# POWER.net
KiCad netlist of a schematic drawn in Altium Designer
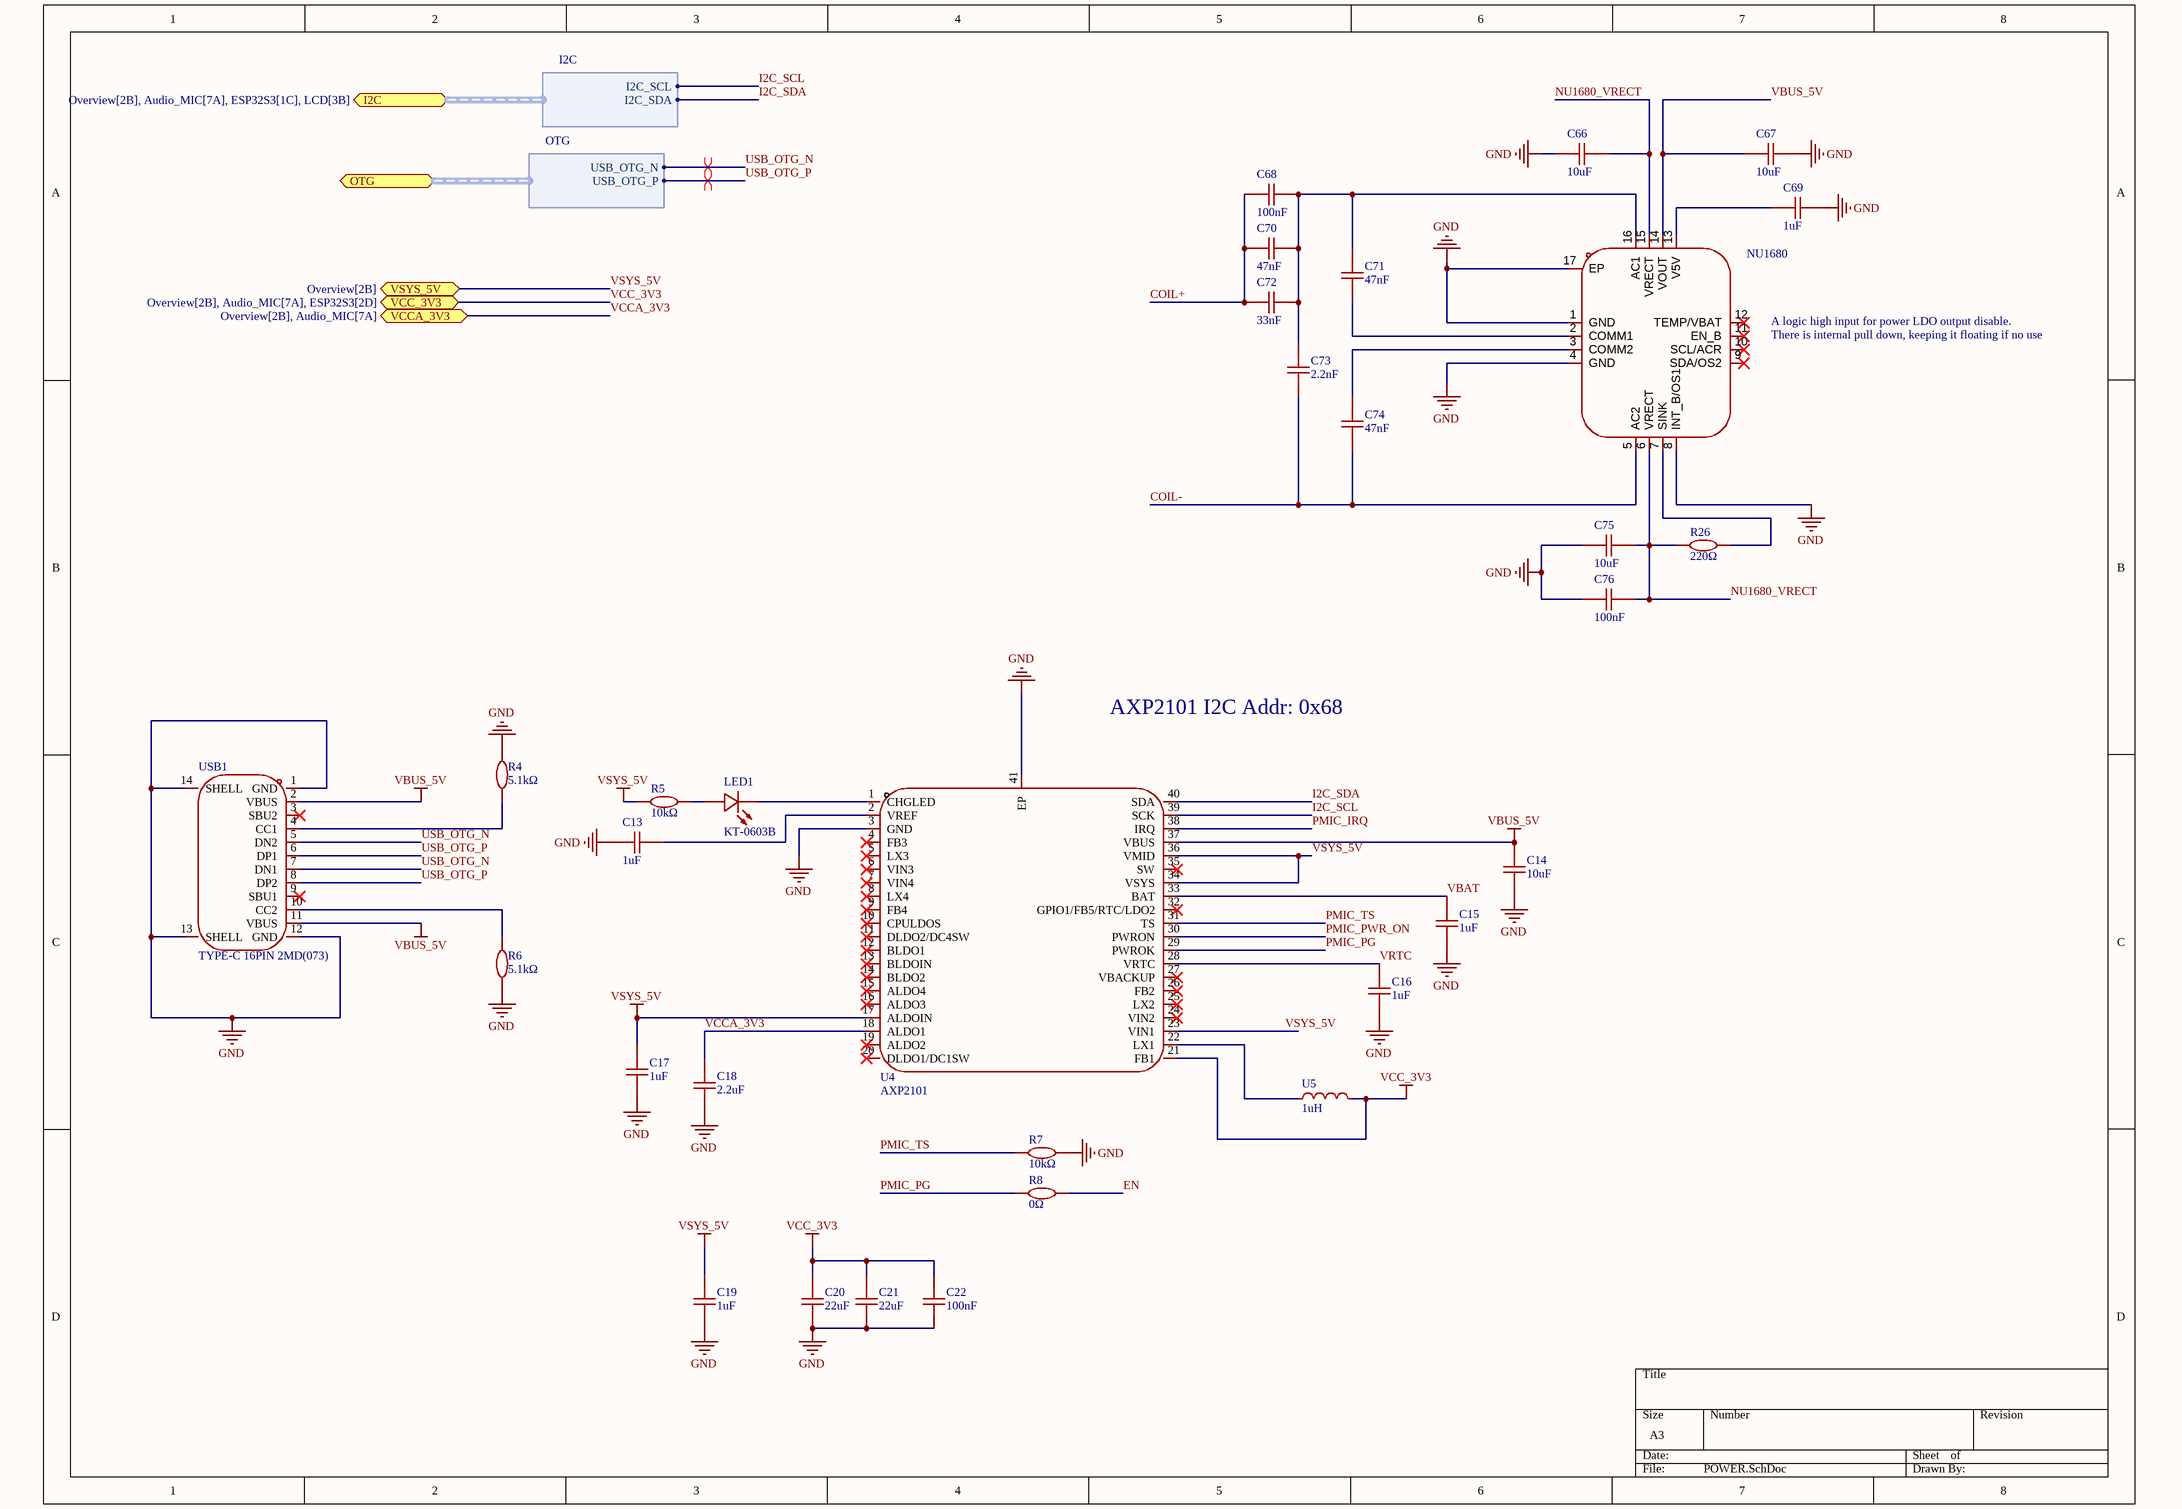
[diagram p0: POWER.SchDoc]

(export (version "E")
  (design (tool "Eeschema 10.0.6"))
  (components
    (comp (ref "C13")
      (value "1uF")
      (footprint "C0402")
      (description "50V 1uF X5R ±10% 0402 Ceramic Capacitors ROHS")
      (libsource (lib "RLC") (part "1uF"))
    )
    (comp (ref "C14")
      (value "10uF")
      (footprint "C0603")
      (description "10V 10uF X5R ±10% 0603 Ceramic Capacitors ROHS")
      (libsource (lib "RLC") (part "10uF"))
    )
    (comp (ref "C15")
      (value "1uF")
      (footprint "C0402")
      (description "50V 1uF X5R ±10% 0402 Ceramic Capacitors ROHS")
      (libsource (lib "RLC") (part "1uF"))
    )
    (comp (ref "C16")
      (value "1uF")
      (footprint "C0402")
      (description "50V 1uF X5R ±10% 0402 Ceramic Capacitors ROHS")
      (libsource (lib "RLC") (part "1uF"))
    )
    (comp (ref "C17")
      (value "1uF")
      (footprint "C0402")
      (description "50V 1uF X5R ±10% 0402 Ceramic Capacitors ROHS")
      (libsource (lib "RLC") (part "1uF"))
    )
    (comp (ref "C18")
      (value "2.2uF")
      (footprint "C0402")
      (description "50V 2.2uF NP0 0402 Ceramic Capacitors ROHS")
      (libsource (lib "RLC") (part "2.2uF"))
    )
    (comp (ref "C19")
      (value "1uF")
      (footprint "C0402")
      (description "50V 1uF X5R ±10% 0402 Ceramic Capacitors ROHS")
      (libsource (lib "RLC") (part "1uF"))
    )
    (comp (ref "C20")
      (value "22uF")
      (footprint "C0603")
      (description "16V 22uF X5R ±20% 0603 Ceramic Capacitors ROHS")
      (libsource (lib "RLC") (part "22uF"))
    )
    (comp (ref "C21")
      (value "22uF")
      (footprint "C0603")
      (description "16V 22uF X5R ±20% 0603 Ceramic Capacitors ROHS")
      (libsource (lib "RLC") (part "22uF"))
    )
    (comp (ref "C22")
      (value "100nF")
      (footprint "C0402")
      (description "50V 100nF X7R ±10% 0402 Ceramic Capacitors ROHS")
      (libsource (lib "RLC") (part "100nF"))
    )
    (comp (ref "C66")
      (value "10uF")
      (footprint "C0603")
      (description "10V 10uF X5R ±10% 0603 Ceramic Capacitors ROHS")
      (libsource (lib "RLC") (part "10uF"))
    )
    (comp (ref "C67")
      (value "10uF")
      (footprint "C0603")
      (description "10V 10uF X5R ±10% 0603 Ceramic Capacitors ROHS")
      (libsource (lib "RLC") (part "10uF"))
    )
    (comp (ref "C68")
      (value "100nF")
      (footprint "C0402")
      (description "50V 100nF X7R ±10% 0402 Ceramic Capacitors ROHS")
      (libsource (lib "RLC") (part "100nF"))
    )
    (comp (ref "C69")
      (value "1uF")
      (footprint "C0402")
      (description "50V 1uF X5R ±10% 0402 Ceramic Capacitors ROHS")
      (libsource (lib "RLC") (part "1uF"))
    )
    (comp (ref "C70")
      (value "47nF")
      (footprint "C0402")
      (description "25V 470nF X5R ±10% 0402 Ceramic Capacitors ROHS")
      (libsource (lib "RLC") (part "470nF"))
    )
    (comp (ref "C71")
      (value "47nF")
      (footprint "C0402")
      (description "25V 470nF X5R ±10% 0402 Ceramic Capacitors ROHS")
      (libsource (lib "RLC") (part "470nF"))
    )
    (comp (ref "C72")
      (value "33nF")
      (footprint "C0402")
      (description "25V 470nF X5R ±10% 0402 Ceramic Capacitors ROHS")
      (libsource (lib "RLC") (part "470nF"))
    )
    (comp (ref "C73")
      (value "2.2nF")
      (footprint "C0402")
      (description "50V 2.2uF NP0 0402 Ceramic Capacitors ROHS")
      (libsource (lib "RLC") (part "2.2uF"))
    )
    (comp (ref "C74")
      (value "47nF")
      (footprint "C0402")
      (description "25V 470nF X5R ±10% 0402 Ceramic Capacitors ROHS")
      (libsource (lib "RLC") (part "470nF"))
    )
    (comp (ref "C75")
      (value "10uF")
      (footprint "C0603")
      (description "10V 10uF X5R ±10% 0603 Ceramic Capacitors ROHS")
      (libsource (lib "RLC") (part "10uF"))
    )
    (comp (ref "C76")
      (value "100nF")
      (footprint "C0402")
      (description "50V 100nF X7R ±10% 0402 Ceramic Capacitors ROHS")
      (libsource (lib "RLC") (part "100nF"))
    )
    (comp (ref "LED1")
      (value "KT-0603B")
      (footprint "LED0603-BL")
      (description "30mA 2.6V~3.2V Blue 0603 LED Indication - Discrete ROHS")
      (libsource (lib "LED") (part "KT-0603B"))
    )
    (comp (ref "R4")
      (value "5.1kΩ")
      (footprint "R0402")
      (description "5.1kΩ 62.5mW 50V ±100ppm/℃ Thick Film Resistor ±1% 0402 Chip Resistor - Surface Mount ROHS")
      (libsource (lib "RLC") (part "5.1kΩ"))
    )
    (comp (ref "R5")
      (value "10kΩ")
      (footprint "R0402")
      (description "62.5mW 10kΩ 50V ±100ppm/℃ Thick Film Resistor ±1% 0402 Chip Resistor - Surface Mount ROHS")
      (libsource (lib "RLC") (part "10kΩ"))
    )
    (comp (ref "R6")
      (value "5.1kΩ")
      (footprint "R0402")
      (description "5.1kΩ 62.5mW 50V ±100ppm/℃ Thick Film Resistor ±1% 0402 Chip Resistor - Surface Mount ROHS")
      (libsource (lib "RLC") (part "5.1kΩ"))
    )
    (comp (ref "R7")
      (value "10kΩ")
      (footprint "R0402")
      (description "62.5mW 10kΩ 50V ±100ppm/℃ Thick Film Resistor ±1% 0402 Chip Resistor - Surface Mount ROHS")
      (libsource (lib "RLC") (part "10kΩ"))
    )
    (comp (ref "R8")
      (value "0Ω")
      (footprint "R0402")
      (description "0Ω 62.5mW 50V Thick Film Resistor ±1% 0402 Chip Resistor - Surface Mount ROHS")
      (libsource (lib "RLC") (part "0Ω"))
    )
    (comp (ref "R26")
      (value "220Ω")
      (footprint "R0402")
      (description "小尺寸、重量轻。降低组装成本,与贴片机匹配。适用于波峰焊和回流焊")
      (libsource (lib "RLC") (part "220Ω"))
    )
    (comp (ref "U4")
      (value "AXP2101")
      (footprint "QFN-40_L5.0-W5.0-P0.40-TL-EP3.4")
      (libsource (lib "IC") (part "AXP2101"))
    )
    (comp (ref "U5")
      (value "1uH")
      (footprint "IND-SMD_L2.5-W2.0_WPN252012H")
      (libsource (lib "RLC") (part "WPN252012H1R0MT"))
    )
    (comp (ref "U12")
      (value "NU1680")
      (footprint "QFN-16_L3.0-W3.0-P0.50-TL-EP1.9")
      (description "无线充电")
      (libsource (lib "IC") (part "NU1680"))
    )
    (comp (ref "USB1")
      (value "TYPE-C 16PIN 2MD(073)")
      (footprint "USB-C-SMD_TYPE-C-6PIN-2MD-073")
      (description "16pin type-c")
      (libsource (lib "Connector") (part "TYPE-C 16PIN 2MD(073)"))
    )
  )
  (nets
    (net (code "3") (name "/COIL+") (class "Default")
      (node (ref "C68") (pin "2") (pinfunction "2_2") (pintype "passive"))
      (node (ref "C70") (pin "2") (pinfunction "2_2") (pintype "passive"))
      (node (ref "C72") (pin "2") (pinfunction "2_2") (pintype "passive"))
    )
    (net (code "4") (name "/COIL-") (class "Default")
      (node (ref "C73") (pin "1") (pinfunction "1_1") (pintype "passive"))
      (node (ref "C74") (pin "1") (pinfunction "1_1") (pintype "passive"))
      (node (ref "U12") (pin "5") (pinfunction "AC2_5") (pintype "passive"))
    )
    (net (code "5") (name "/EN") (class "Default")
      (node (ref "R8") (pin "2") (pinfunction "2_2") (pintype "passive"))
    )
    (net (code "6") (name "/I2C_SCL") (class "Default")
      (node (ref "U4") (pin "39") (pinfunction "SCK_39") (pintype "passive"))
    )
    (net (code "7") (name "/I2C_SDA") (class "Default")
      (node (ref "U4") (pin "40") (pinfunction "SDA_40") (pintype "passive"))
    )
    (net (code "8") (name "/NU1680_VRECT") (class "Default")
      (node (ref "C66") (pin "1") (pinfunction "1_1") (pintype "passive"))
      (node (ref "C75") (pin "1") (pinfunction "1_1") (pintype "passive"))
      (node (ref "C76") (pin "1") (pinfunction "1_1") (pintype "passive"))
      (node (ref "R26") (pin "1") (pinfunction "1_1") (pintype "passive"))
      (node (ref "U12") (pin "15") (pinfunction "VRECT_15") (pintype "passive"))
      (node (ref "U12") (pin "6") (pinfunction "VRECT_6") (pintype "passive"))
    )
    (net (code "9") (name "/PMIC_IRQ") (class "Default")
      (node (ref "U4") (pin "38") (pinfunction "IRQ_38") (pintype "passive"))
    )
    (net (code "10") (name "/PMIC_PG") (class "Default")
      (node (ref "R8") (pin "1") (pinfunction "1_1") (pintype "passive"))
      (node (ref "U4") (pin "29") (pinfunction "PWROK_29") (pintype "passive"))
    )
    (net (code "11") (name "/PMIC_PWR_ON") (class "Default")
      (node (ref "U4") (pin "30") (pinfunction "PWRON_30") (pintype "passive"))
    )
    (net (code "12") (name "/PMIC_TS") (class "Default")
      (node (ref "R7") (pin "1") (pinfunction "1_1") (pintype "passive"))
      (node (ref "U4") (pin "31") (pinfunction "TS_31") (pintype "passive"))
    )
    (net (code "13") (name "/USB_OTG_N") (class "Default")
      (node (ref "USB1") (pin "5") (pinfunction "DN2_5") (pintype "passive"))
      (node (ref "USB1") (pin "7") (pinfunction "DN1_7") (pintype "passive"))
    )
    (net (code "14") (name "/USB_OTG_P") (class "Default")
      (node (ref "USB1") (pin "6") (pinfunction "DP1_6") (pintype "passive"))
      (node (ref "USB1") (pin "8") (pinfunction "DP2_8") (pintype "passive"))
    )
    (net (code "15") (name "/VBAT") (class "Default")
      (node (ref "C15") (pin "2") (pinfunction "2_2") (pintype "passive"))
      (node (ref "U4") (pin "33") (pinfunction "BAT_33") (pintype "passive"))
    )
    (net (code "16") (name "/VCCA_3V3") (class "Default")
      (node (ref "C18") (pin "2") (pinfunction "2_2") (pintype "passive"))
      (node (ref "U4") (pin "18") (pinfunction "ALDO1_18") (pintype "passive"))
    )
    (net (code "17") (name "/VRTC") (class "Default")
      (node (ref "C16") (pin "2") (pinfunction "2_2") (pintype "passive"))
      (node (ref "U4") (pin "28") (pinfunction "VRTC_28") (pintype "passive"))
    )
    (net (code "20") (name "GND") (class "Default")
      (node (ref "C13") (pin "1") (pinfunction "1_1") (pintype "passive"))
      (node (ref "C14") (pin "1") (pinfunction "1_1") (pintype "passive"))
      (node (ref "C15") (pin "1") (pinfunction "1_1") (pintype "passive"))
      (node (ref "C16") (pin "1") (pinfunction "1_1") (pintype "passive"))
      (node (ref "C17") (pin "1") (pinfunction "1_1") (pintype "passive"))
      (node (ref "C18") (pin "1") (pinfunction "1_1") (pintype "passive"))
      (node (ref "C19") (pin "1") (pinfunction "1_1") (pintype "passive"))
      (node (ref "C20") (pin "1") (pinfunction "1_1") (pintype "passive"))
      (node (ref "C21") (pin "1") (pinfunction "1_1") (pintype "passive"))
      (node (ref "C22") (pin "1") (pinfunction "1_1") (pintype "passive"))
      (node (ref "C66") (pin "2") (pinfunction "2_2") (pintype "passive"))
      (node (ref "C67") (pin "1") (pinfunction "1_1") (pintype "passive"))
      (node (ref "C69") (pin "1") (pinfunction "1_1") (pintype "passive"))
      (node (ref "C75") (pin "2") (pinfunction "2_2") (pintype "passive"))
      (node (ref "C76") (pin "2") (pinfunction "2_2") (pintype "passive"))
      (node (ref "R4") (pin "2") (pinfunction "2_2") (pintype "passive"))
      (node (ref "R6") (pin "1") (pinfunction "1_1") (pintype "passive"))
      (node (ref "R7") (pin "2") (pinfunction "2_2") (pintype "passive"))
      (node (ref "U12") (pin "1") (pinfunction "GND_1") (pintype "passive"))
      (node (ref "U12") (pin "17") (pinfunction "EP_17") (pintype "passive"))
      (node (ref "U12") (pin "4") (pinfunction "GND_4") (pintype "passive"))
      (node (ref "U12") (pin "8") (pinfunction "INT_B/OS1_8") (pintype "passive"))
      (node (ref "U4") (pin "3") (pinfunction "GND_3") (pintype "passive"))
      (node (ref "U4") (pin "41") (pinfunction "EP_41") (pintype "passive"))
      (node (ref "USB1") (pin "1") (pinfunction "GND_1") (pintype "passive"))
      (node (ref "USB1") (pin "12") (pinfunction "GND_12") (pintype "passive"))
      (node (ref "USB1") (pin "13") (pinfunction "SHELL_13") (pintype "passive"))
      (node (ref "USB1") (pin "14") (pinfunction "SHELL_14") (pintype "passive"))
    )
    (net (code "21") (name "Net-(LED1-A)") (class "Default")
      (node (ref "LED1") (pin "2") (pinfunction "A_2") (pintype "passive"))
      (node (ref "R5") (pin "2") (pinfunction "2_2") (pintype "passive"))
    )
    (net (code "22") (name "Net-(LED1-K)") (class "Default")
      (node (ref "LED1") (pin "1") (pinfunction "K_1") (pintype "passive"))
      (node (ref "U4") (pin "1") (pinfunction "CHGLED_1") (pintype "passive"))
    )
    (net (code "23") (name "Net-(U4-LX1)") (class "Default")
      (node (ref "U4") (pin "22") (pinfunction "LX1_22") (pintype "passive"))
      (node (ref "U5") (pin "1") (pinfunction "1_1") (pintype "passive"))
    )
    (net (code "24") (name "Net-(U4-VREF)") (class "Default")
      (node (ref "C13") (pin "2") (pinfunction "2_2") (pintype "passive"))
      (node (ref "U4") (pin "2") (pinfunction "VREF_2") (pintype "passive"))
    )
    (net (code "25") (name "Net-(U12-AC1)") (class "Default")
      (node (ref "C68") (pin "1") (pinfunction "1_1") (pintype "passive"))
      (node (ref "C70") (pin "1") (pinfunction "1_1") (pintype "passive"))
      (node (ref "C71") (pin "2") (pinfunction "2_2") (pintype "passive"))
      (node (ref "C72") (pin "1") (pinfunction "1_1") (pintype "passive"))
      (node (ref "C73") (pin "2") (pinfunction "2_2") (pintype "passive"))
      (node (ref "U12") (pin "16") (pinfunction "AC1_16") (pintype "passive"))
    )
    (net (code "26") (name "Net-(U12-COMM1)") (class "Default")
      (node (ref "C71") (pin "1") (pinfunction "1_1") (pintype "passive"))
      (node (ref "U12") (pin "2") (pinfunction "COMM1_2") (pintype "passive"))
    )
    (net (code "27") (name "Net-(U12-COMM2)") (class "Default")
      (node (ref "C74") (pin "2") (pinfunction "2_2") (pintype "passive"))
      (node (ref "U12") (pin "3") (pinfunction "COMM2_3") (pintype "passive"))
    )
    (net (code "28") (name "Net-(U12-SINK)") (class "Default")
      (node (ref "R26") (pin "2") (pinfunction "2_2") (pintype "passive"))
      (node (ref "U12") (pin "7") (pinfunction "SINK_7") (pintype "passive"))
    )
    (net (code "29") (name "Net-(U12-V5V)") (class "Default")
      (node (ref "C69") (pin "2") (pinfunction "2_2") (pintype "passive"))
      (node (ref "U12") (pin "13") (pinfunction "V5V_13") (pintype "passive"))
    )
    (net (code "30") (name "Net-(USB1-CC1)") (class "Default")
      (node (ref "R4") (pin "1") (pinfunction "1_1") (pintype "passive"))
      (node (ref "USB1") (pin "4") (pinfunction "CC1_4") (pintype "passive"))
    )
    (net (code "31") (name "Net-(USB1-CC2)") (class "Default")
      (node (ref "R6") (pin "2") (pinfunction "2_2") (pintype "passive"))
      (node (ref "USB1") (pin "10") (pinfunction "CC2_10") (pintype "passive"))
    )
    (net (code "32") (name "VBUS_5V") (class "Default")
      (node (ref "C14") (pin "2") (pinfunction "2_2") (pintype "passive"))
      (node (ref "C67") (pin "2") (pinfunction "2_2") (pintype "passive"))
      (node (ref "U12") (pin "14") (pinfunction "VOUT_14") (pintype "passive"))
      (node (ref "U4") (pin "37") (pinfunction "VBUS_37") (pintype "passive"))
      (node (ref "USB1") (pin "11") (pinfunction "VBUS_11") (pintype "passive"))
      (node (ref "USB1") (pin "2") (pinfunction "VBUS_2") (pintype "passive"))
    )
    (net (code "33") (name "VCC_3V3") (class "Default")
      (node (ref "C20") (pin "2") (pinfunction "2_2") (pintype "passive"))
      (node (ref "C21") (pin "2") (pinfunction "2_2") (pintype "passive"))
      (node (ref "C22") (pin "2") (pinfunction "2_2") (pintype "passive"))
      (node (ref "U4") (pin "21") (pinfunction "FB1_21") (pintype "passive"))
      (node (ref "U5") (pin "2") (pinfunction "2_2") (pintype "passive"))
    )
    (net (code "34") (name "VSYS_5V") (class "Default")
      (node (ref "C17") (pin "2") (pinfunction "2_2") (pintype "passive"))
      (node (ref "C19") (pin "2") (pinfunction "2_2") (pintype "passive"))
      (node (ref "R5") (pin "1") (pinfunction "1_1") (pintype "passive"))
      (node (ref "U4") (pin "17") (pinfunction "ALDOIN_17") (pintype "passive"))
      (node (ref "U4") (pin "23") (pinfunction "VIN1_23") (pintype "passive"))
      (node (ref "U4") (pin "34") (pinfunction "VSYS_34") (pintype "passive"))
      (node (ref "U4") (pin "36") (pinfunction "VMID_36") (pintype "passive"))
    )
    (net (code "35") (name "unconnected-(U4-ALDO2-Pad19)") (class "Default")
      (node (ref "U4") (pin "19") (pinfunction "ALDO2_19") (pintype "passive+no_connect"))
    )
    (net (code "36") (name "unconnected-(U4-ALDO3-Pad16)") (class "Default")
      (node (ref "U4") (pin "16") (pinfunction "ALDO3_16") (pintype "passive+no_connect"))
    )
    (net (code "37") (name "unconnected-(U4-ALDO4-Pad15)") (class "Default")
      (node (ref "U4") (pin "15") (pinfunction "ALDO4_15") (pintype "passive+no_connect"))
    )
    (net (code "38") (name "unconnected-(U4-BLDO1-Pad12)") (class "Default")
      (node (ref "U4") (pin "12") (pinfunction "BLDO1_12") (pintype "passive+no_connect"))
    )
    (net (code "39") (name "unconnected-(U4-BLDO2-Pad14)") (class "Default")
      (node (ref "U4") (pin "14") (pinfunction "BLDO2_14") (pintype "passive+no_connect"))
    )
    (net (code "40") (name "unconnected-(U4-BLDOIN-Pad13)") (class "Default")
      (node (ref "U4") (pin "13") (pinfunction "BLDOIN_13") (pintype "passive+no_connect"))
    )
    (net (code "41") (name "unconnected-(U4-CPULDOS-Pad10)") (class "Default")
      (node (ref "U4") (pin "10") (pinfunction "CPULDOS_10") (pintype "passive+no_connect"))
    )
    (net (code "42") (name "unconnected-(U4-DLDO1{slash}DC1SW-Pad20)") (class "Default")
      (node (ref "U4") (pin "20") (pinfunction "DLDO1/DC1SW_20") (pintype "passive+no_connect"))
    )
    (net (code "43") (name "unconnected-(U4-DLDO2{slash}DC4SW-Pad11)") (class "Default")
      (node (ref "U4") (pin "11") (pinfunction "DLDO2/DC4SW_11") (pintype "passive+no_connect"))
    )
    (net (code "44") (name "unconnected-(U4-FB2-Pad26)") (class "Default")
      (node (ref "U4") (pin "26") (pinfunction "FB2_26") (pintype "passive+no_connect"))
    )
    (net (code "45") (name "unconnected-(U4-FB3-Pad4)") (class "Default")
      (node (ref "U4") (pin "4") (pinfunction "FB3_4") (pintype "passive+no_connect"))
    )
    (net (code "46") (name "unconnected-(U4-FB4-Pad9)") (class "Default")
      (node (ref "U4") (pin "9") (pinfunction "FB4_9") (pintype "passive+no_connect"))
    )
    (net (code "47") (name "unconnected-(U4-GPIO1{slash}FB5{slash}RTC{slash}LDO2-Pad32)") (class "Default")
      (node (ref "U4") (pin "32") (pinfunction "GPIO1/FB5/RTC/LDO2_32") (pintype "passive+no_connect"))
    )
    (net (code "48") (name "unconnected-(U4-LX2-Pad25)") (class "Default")
      (node (ref "U4") (pin "25") (pinfunction "LX2_25") (pintype "passive+no_connect"))
    )
    (net (code "49") (name "unconnected-(U4-LX3-Pad5)") (class "Default")
      (node (ref "U4") (pin "5") (pinfunction "LX3_5") (pintype "passive+no_connect"))
    )
    (net (code "50") (name "unconnected-(U4-LX4-Pad8)") (class "Default")
      (node (ref "U4") (pin "8") (pinfunction "LX4_8") (pintype "passive+no_connect"))
    )
    (net (code "51") (name "unconnected-(U4-SW-Pad35)") (class "Default")
      (node (ref "U4") (pin "35") (pinfunction "SW_35") (pintype "passive+no_connect"))
    )
    (net (code "52") (name "unconnected-(U4-VBACKUP-Pad27)") (class "Default")
      (node (ref "U4") (pin "27") (pinfunction "VBACKUP_27") (pintype "passive+no_connect"))
    )
    (net (code "53") (name "unconnected-(U4-VIN2-Pad24)") (class "Default")
      (node (ref "U4") (pin "24") (pinfunction "VIN2_24") (pintype "passive+no_connect"))
    )
    (net (code "54") (name "unconnected-(U4-VIN3-Pad6)") (class "Default")
      (node (ref "U4") (pin "6") (pinfunction "VIN3_6") (pintype "passive+no_connect"))
    )
    (net (code "55") (name "unconnected-(U4-VIN4-Pad7)") (class "Default")
      (node (ref "U4") (pin "7") (pinfunction "VIN4_7") (pintype "passive+no_connect"))
    )
    (net (code "56") (name "unconnected-(U12-EN_B-Pad11)") (class "Default")
      (node (ref "U12") (pin "11") (pinfunction "EN_B_11") (pintype "passive+no_connect"))
    )
    (net (code "57") (name "unconnected-(U12-SCL{slash}ACR-Pad10)") (class "Default")
      (node (ref "U12") (pin "10") (pinfunction "SCL/ACR_10") (pintype "passive+no_connect"))
    )
    (net (code "58") (name "unconnected-(U12-SDA{slash}OS2-Pad9)") (class "Default")
      (node (ref "U12") (pin "9") (pinfunction "SDA/OS2_9") (pintype "passive+no_connect"))
    )
    (net (code "59") (name "unconnected-(U12-TEMP{slash}VBAT-Pad12)") (class "Default")
      (node (ref "U12") (pin "12") (pinfunction "TEMP/VBAT_12") (pintype "passive+no_connect"))
    )
    (net (code "60") (name "unconnected-(USB1-SBU1-Pad9)") (class "Default")
      (node (ref "USB1") (pin "9") (pinfunction "SBU1_9") (pintype "passive+no_connect"))
    )
    (net (code "61") (name "unconnected-(USB1-SBU2-Pad3)") (class "Default")
      (node (ref "USB1") (pin "3") (pinfunction "SBU2_3") (pintype "passive+no_connect"))
    )
  )
)
